# UDAWA-Aktuator4CH.net
KiCad netlist of a schematic drawn in EAGLE
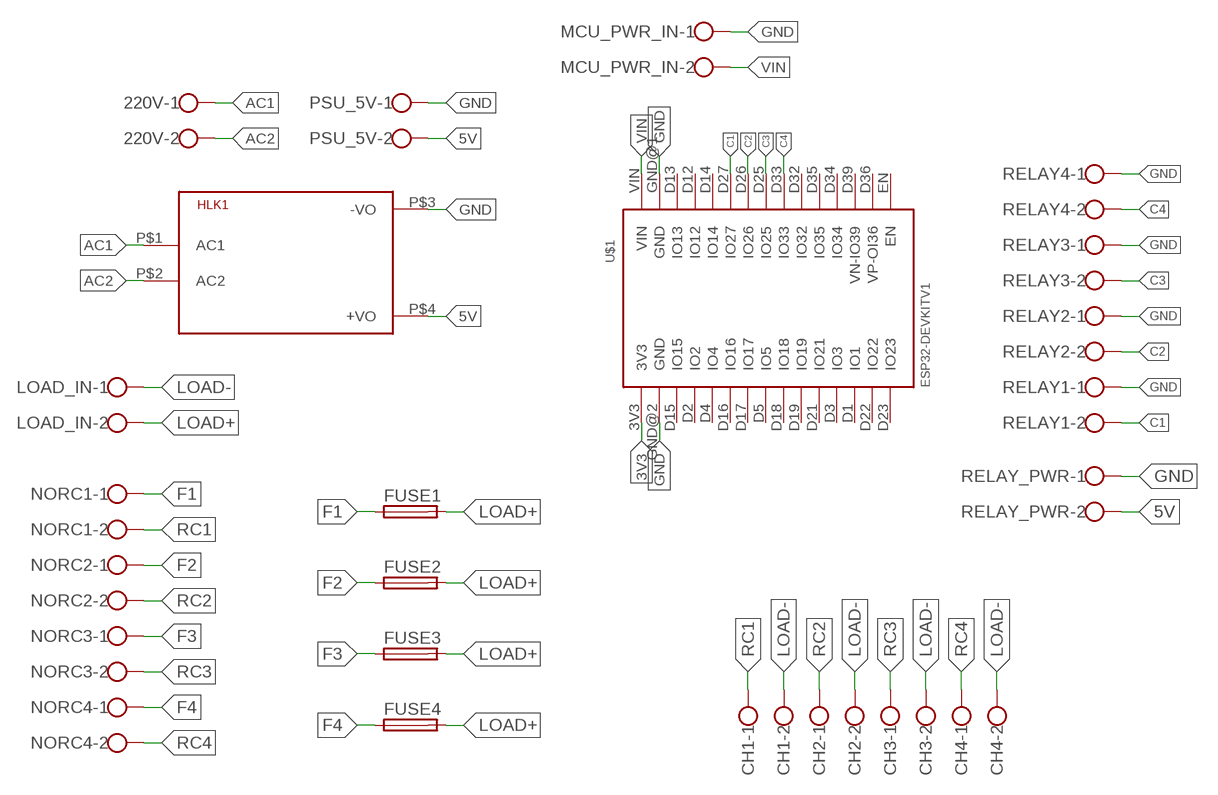
[diagram p0: schematic, sheet 1]

(export (version "E")
  (design (tool "Eeschema 10.0.6"))
  (components
    (comp (ref "220V")
      (value "W237-102")
      (footprint "eagle-import:W237-102")
      (fields (field (name "MPN") "237-102"))
      (libsource (lib "eagle-import") (part "W237-102"))
    )
    (comp (ref "CH1")
      (value "W237-102")
      (footprint "eagle-import:W237-102")
      (fields (field (name "MPN") "237-102"))
      (libsource (lib "eagle-import") (part "W237-102"))
    )
    (comp (ref "CH2")
      (value "W237-102")
      (footprint "eagle-import:W237-102")
      (fields (field (name "MPN") "237-102"))
      (libsource (lib "eagle-import") (part "W237-102"))
    )
    (comp (ref "CH3")
      (value "W237-102")
      (footprint "eagle-import:W237-102")
      (fields (field (name "MPN") "237-102"))
      (libsource (lib "eagle-import") (part "W237-102"))
    )
    (comp (ref "CH4")
      (value "W237-102")
      (footprint "eagle-import:W237-102")
      (fields (field (name "MPN") "237-102"))
      (libsource (lib "eagle-import") (part "W237-102"))
    )
    (comp (ref "FUSE1")
      (value "SH22,5A")
      (footprint "eagle-import:SH22,5A")
      (fields (field (name "MPN") "0031.7701.11"))
      (libsource (lib "eagle-import") (part "SH22,5A"))
    )
    (comp (ref "FUSE2")
      (value "SH22,5A")
      (footprint "eagle-import:SH22,5A")
      (fields (field (name "MPN") "0031.7701.11"))
      (libsource (lib "eagle-import") (part "SH22,5A"))
    )
    (comp (ref "FUSE3")
      (value "SH22,5A")
      (footprint "eagle-import:SH22,5A")
      (fields (field (name "MPN") "0031.7701.11"))
      (libsource (lib "eagle-import") (part "SH22,5A"))
    )
    (comp (ref "FUSE4")
      (value "SH22,5A")
      (footprint "eagle-import:SH22,5A")
      (fields (field (name "MPN") "0031.7701.11"))
      (libsource (lib "eagle-import") (part "SH22,5A"))
    )
    (comp (ref "HLK1")
      (value "HLK-PM013W")
      (footprint "eagle-import:HLK-PM01")
      (libsource (lib "eagle-import") (part "HLK-PM013W"))
    )
    (comp (ref "LOAD_IN")
      (value "W237-102")
      (footprint "eagle-import:W237-102")
      (fields (field (name "MPN") "237-102"))
      (libsource (lib "eagle-import") (part "W237-102"))
    )
    (comp (ref "MCU_PWR_IN")
      (value "W237-102")
      (footprint "eagle-import:W237-102")
      (fields (field (name "MPN") "237-102"))
      (libsource (lib "eagle-import") (part "W237-102"))
    )
    (comp (ref "NORC1")
      (value "W237-102")
      (footprint "eagle-import:W237-102")
      (fields (field (name "MPN") "237-102"))
      (libsource (lib "eagle-import") (part "W237-102"))
    )
    (comp (ref "NORC2")
      (value "W237-102")
      (footprint "eagle-import:W237-102")
      (fields (field (name "MPN") "237-102"))
      (libsource (lib "eagle-import") (part "W237-102"))
    )
    (comp (ref "NORC3")
      (value "W237-102")
      (footprint "eagle-import:W237-102")
      (fields (field (name "MPN") "237-102"))
      (libsource (lib "eagle-import") (part "W237-102"))
    )
    (comp (ref "NORC4")
      (value "W237-102")
      (footprint "eagle-import:W237-102")
      (fields (field (name "MPN") "237-102"))
      (libsource (lib "eagle-import") (part "W237-102"))
    )
    (comp (ref "PSU_5V")
      (value "W237-102")
      (footprint "eagle-import:W237-102")
      (fields (field (name "MPN") "237-102"))
      (libsource (lib "eagle-import") (part "W237-102"))
    )
    (comp (ref "RELAY1")
      (value "W237-102")
      (footprint "eagle-import:W237-102")
      (fields (field (name "MPN") "237-102"))
      (libsource (lib "eagle-import") (part "W237-102"))
    )
    (comp (ref "RELAY2")
      (value "W237-102")
      (footprint "eagle-import:W237-102")
      (fields (field (name "MPN") "237-102"))
      (libsource (lib "eagle-import") (part "W237-102"))
    )
    (comp (ref "RELAY3")
      (value "W237-102")
      (footprint "eagle-import:W237-102")
      (fields (field (name "MPN") "237-102"))
      (libsource (lib "eagle-import") (part "W237-102"))
    )
    (comp (ref "RELAY4")
      (value "W237-102")
      (footprint "eagle-import:W237-102")
      (fields (field (name "MPN") "237-102"))
      (libsource (lib "eagle-import") (part "W237-102"))
    )
    (comp (ref "RELAY_PWR")
      (value "W237-102")
      (footprint "eagle-import:W237-102")
      (fields (field (name "MPN") "237-102"))
      (libsource (lib "eagle-import") (part "W237-102"))
    )
    (comp (ref "U$1")
      (value "ESP32DEVKITV1")
      (footprint "eagle-import:ESP32-DEVKITV1")
      (libsource (lib "eagle-import") (part "ESP32DEVKITV1"))
    )
  )
  (nets
    (net (code "1") (name "3V3") (class "Default")
      (node (ref "U$1") (pin "3V3") (pinfunction "3V3_3V3") (pintype "bidirectional"))
    )
    (net (code "2") (name "5V") (class "Default")
      (node (ref "HLK1") (pin "P$4") (pinfunction "+VO_P$4") (pintype "bidirectional"))
      (node (ref "PSU_5V") (pin "2") (pinfunction "KL_2") (pintype "passive"))
      (node (ref "RELAY_PWR") (pin "2") (pinfunction "KL_2") (pintype "passive"))
    )
    (net (code "3") (name "AC1") (class "Default")
      (node (ref "220V") (pin "1") (pinfunction "KL_1") (pintype "passive"))
      (node (ref "HLK1") (pin "P$1") (pinfunction "AC1_P$1") (pintype "bidirectional"))
    )
    (net (code "4") (name "AC2") (class "Default")
      (node (ref "220V") (pin "2") (pinfunction "KL_2") (pintype "passive"))
      (node (ref "HLK1") (pin "P$2") (pinfunction "AC2_P$2") (pintype "bidirectional"))
    )
    (net (code "5") (name "C1") (class "Default")
      (node (ref "RELAY1") (pin "2") (pinfunction "KL_2") (pintype "passive"))
      (node (ref "U$1") (pin "D27") (pinfunction "IO27_D27") (pintype "bidirectional"))
    )
    (net (code "6") (name "C2") (class "Default")
      (node (ref "RELAY2") (pin "2") (pinfunction "KL_2") (pintype "passive"))
      (node (ref "U$1") (pin "D26") (pinfunction "IO26_D26") (pintype "bidirectional"))
    )
    (net (code "7") (name "C3") (class "Default")
      (node (ref "RELAY3") (pin "2") (pinfunction "KL_2") (pintype "passive"))
      (node (ref "U$1") (pin "D25") (pinfunction "IO25_D25") (pintype "bidirectional"))
    )
    (net (code "8") (name "C4") (class "Default")
      (node (ref "RELAY4") (pin "2") (pinfunction "KL_2") (pintype "passive"))
      (node (ref "U$1") (pin "D33") (pinfunction "IO33_D33") (pintype "bidirectional"))
    )
    (net (code "9") (name "F1") (class "Default")
      (node (ref "FUSE1") (pin "1") (pinfunction "1_1") (pintype "passive"))
      (node (ref "NORC1") (pin "1") (pinfunction "KL_1") (pintype "passive"))
    )
    (net (code "10") (name "F2") (class "Default")
      (node (ref "FUSE2") (pin "1") (pinfunction "1_1") (pintype "passive"))
      (node (ref "NORC2") (pin "1") (pinfunction "KL_1") (pintype "passive"))
    )
    (net (code "11") (name "F3") (class "Default")
      (node (ref "FUSE3") (pin "1") (pinfunction "1_1") (pintype "passive"))
      (node (ref "NORC3") (pin "1") (pinfunction "KL_1") (pintype "passive"))
    )
    (net (code "12") (name "F4") (class "Default")
      (node (ref "FUSE4") (pin "1") (pinfunction "1_1") (pintype "passive"))
      (node (ref "NORC4") (pin "1") (pinfunction "KL_1") (pintype "passive"))
    )
    (net (code "13") (name "GND") (class "Default")
      (node (ref "HLK1") (pin "P$3") (pinfunction "-VO_P$3") (pintype "bidirectional"))
      (node (ref "MCU_PWR_IN") (pin "1") (pinfunction "KL_1") (pintype "passive"))
      (node (ref "PSU_5V") (pin "1") (pinfunction "KL_1") (pintype "passive"))
      (node (ref "RELAY1") (pin "1") (pinfunction "KL_1") (pintype "passive"))
      (node (ref "RELAY2") (pin "1") (pinfunction "KL_1") (pintype "passive"))
      (node (ref "RELAY3") (pin "1") (pinfunction "KL_1") (pintype "passive"))
      (node (ref "RELAY4") (pin "1") (pinfunction "KL_1") (pintype "passive"))
      (node (ref "RELAY_PWR") (pin "1") (pinfunction "KL_1") (pintype "passive"))
      (node (ref "U$1") (pin "GND@1") (pinfunction "GND_GND@1") (pintype "bidirectional"))
      (node (ref "U$1") (pin "GND@2") (pinfunction "GND_GND@2") (pintype "bidirectional"))
    )
    (net (code "14") (name "LOAD+") (class "Default")
      (node (ref "FUSE1") (pin "2") (pinfunction "2_2") (pintype "passive"))
      (node (ref "FUSE2") (pin "2") (pinfunction "2_2") (pintype "passive"))
      (node (ref "FUSE3") (pin "2") (pinfunction "2_2") (pintype "passive"))
      (node (ref "FUSE4") (pin "2") (pinfunction "2_2") (pintype "passive"))
      (node (ref "LOAD_IN") (pin "2") (pinfunction "KL_2") (pintype "passive"))
    )
    (net (code "15") (name "LOAD-") (class "Default")
      (node (ref "CH1") (pin "2") (pinfunction "KL_2") (pintype "passive"))
      (node (ref "CH2") (pin "2") (pinfunction "KL_2") (pintype "passive"))
      (node (ref "CH3") (pin "2") (pinfunction "KL_2") (pintype "passive"))
      (node (ref "CH4") (pin "2") (pinfunction "KL_2") (pintype "passive"))
      (node (ref "LOAD_IN") (pin "1") (pinfunction "KL_1") (pintype "passive"))
    )
    (net (code "16") (name "RC1") (class "Default")
      (node (ref "CH1") (pin "1") (pinfunction "KL_1") (pintype "passive"))
      (node (ref "NORC1") (pin "2") (pinfunction "KL_2") (pintype "passive"))
    )
    (net (code "17") (name "RC2") (class "Default")
      (node (ref "CH2") (pin "1") (pinfunction "KL_1") (pintype "passive"))
      (node (ref "NORC2") (pin "2") (pinfunction "KL_2") (pintype "passive"))
    )
    (net (code "18") (name "RC3") (class "Default")
      (node (ref "CH3") (pin "1") (pinfunction "KL_1") (pintype "passive"))
      (node (ref "NORC3") (pin "2") (pinfunction "KL_2") (pintype "passive"))
    )
    (net (code "19") (name "RC4") (class "Default")
      (node (ref "CH4") (pin "1") (pinfunction "KL_1") (pintype "passive"))
      (node (ref "NORC4") (pin "2") (pinfunction "KL_2") (pintype "passive"))
    )
    (net (code "20") (name "VIN") (class "Default")
      (node (ref "MCU_PWR_IN") (pin "2") (pinfunction "KL_2") (pintype "passive"))
      (node (ref "U$1") (pin "VIN") (pinfunction "VIN_VIN") (pintype "bidirectional"))
    )
    (net (code "21") (name "unconnected-(U$1-IO1-PadD1)") (class "Default")
      (node (ref "U$1") (pin "D1") (pinfunction "IO1_D1") (pintype "bidirectional"))
    )
    (net (code "22") (name "unconnected-(U$1-IO2-PadD2)") (class "Default")
      (node (ref "U$1") (pin "D2") (pinfunction "IO2_D2") (pintype "bidirectional"))
    )
    (net (code "23") (name "unconnected-(U$1-IO3-PadD3)") (class "Default")
      (node (ref "U$1") (pin "D3") (pinfunction "IO3_D3") (pintype "bidirectional"))
    )
    (net (code "24") (name "unconnected-(U$1-IO4-PadD4)") (class "Default")
      (node (ref "U$1") (pin "D4") (pinfunction "IO4_D4") (pintype "bidirectional"))
    )
    (net (code "25") (name "unconnected-(U$1-IO5-PadD5)") (class "Default")
      (node (ref "U$1") (pin "D5") (pinfunction "IO5_D5") (pintype "bidirectional"))
    )
    (net (code "26") (name "unconnected-(U$1-IO12-PadD12)") (class "Default")
      (node (ref "U$1") (pin "D12") (pinfunction "IO12_D12") (pintype "bidirectional"))
    )
    (net (code "27") (name "unconnected-(U$1-IO13-PadD13)") (class "Default")
      (node (ref "U$1") (pin "D13") (pinfunction "IO13_D13") (pintype "bidirectional"))
    )
    (net (code "28") (name "unconnected-(U$1-IO14-PadD14)") (class "Default")
      (node (ref "U$1") (pin "D14") (pinfunction "IO14_D14") (pintype "bidirectional"))
    )
    (net (code "29") (name "unconnected-(U$1-IO15-PadD15)") (class "Default")
      (node (ref "U$1") (pin "D15") (pinfunction "IO15_D15") (pintype "bidirectional"))
    )
    (net (code "30") (name "unconnected-(U$1-IO16-PadD16)") (class "Default")
      (node (ref "U$1") (pin "D16") (pinfunction "IO16_D16") (pintype "bidirectional"))
    )
    (net (code "31") (name "unconnected-(U$1-IO17-PadD17)") (class "Default")
      (node (ref "U$1") (pin "D17") (pinfunction "IO17_D17") (pintype "bidirectional"))
    )
    (net (code "32") (name "unconnected-(U$1-IO18-PadD18)") (class "Default")
      (node (ref "U$1") (pin "D18") (pinfunction "IO18_D18") (pintype "bidirectional"))
    )
    (net (code "33") (name "unconnected-(U$1-IO19-PadD19)") (class "Default")
      (node (ref "U$1") (pin "D19") (pinfunction "IO19_D19") (pintype "bidirectional"))
    )
    (net (code "34") (name "unconnected-(U$1-IO21-PadD21)") (class "Default")
      (node (ref "U$1") (pin "D21") (pinfunction "IO21_D21") (pintype "bidirectional"))
    )
    (net (code "35") (name "unconnected-(U$1-IO22-PadD22)") (class "Default")
      (node (ref "U$1") (pin "D22") (pinfunction "IO22_D22") (pintype "bidirectional"))
    )
    (net (code "36") (name "unconnected-(U$1-IO23-PadD23)") (class "Default")
      (node (ref "U$1") (pin "D23") (pinfunction "IO23_D23") (pintype "bidirectional"))
    )
    (net (code "37") (name "unconnected-(U$1-IO32-PadD32)") (class "Default")
      (node (ref "U$1") (pin "D32") (pinfunction "IO32_D32") (pintype "bidirectional"))
    )
    (net (code "38") (name "unconnected-(U$1-IO34-PadD34)") (class "Default")
      (node (ref "U$1") (pin "D34") (pinfunction "IO34_D34") (pintype "bidirectional"))
    )
    (net (code "39") (name "unconnected-(U$1-IO35-PadD35)") (class "Default")
      (node (ref "U$1") (pin "D35") (pinfunction "IO35_D35") (pintype "bidirectional"))
    )
    (net (code "40") (name "unconnected-(U$1-PadEN)") (class "Default")
      (node (ref "U$1") (pin "EN") (pinfunction "EN_EN") (pintype "bidirectional"))
    )
    (net (code "41") (name "unconnected-(U$1-VN-IO39-PadD39)") (class "Default")
      (node (ref "U$1") (pin "D39") (pinfunction "VN-IO39_D39") (pintype "bidirectional"))
    )
    (net (code "42") (name "unconnected-(U$1-VP-OI36-PadD36)") (class "Default")
      (node (ref "U$1") (pin "D36") (pinfunction "VP-OI36_D36") (pintype "bidirectional"))
    )
  )
)
